# ensmartening.net
KiCad netlist of a schematic drawn in EasyEDA Pro
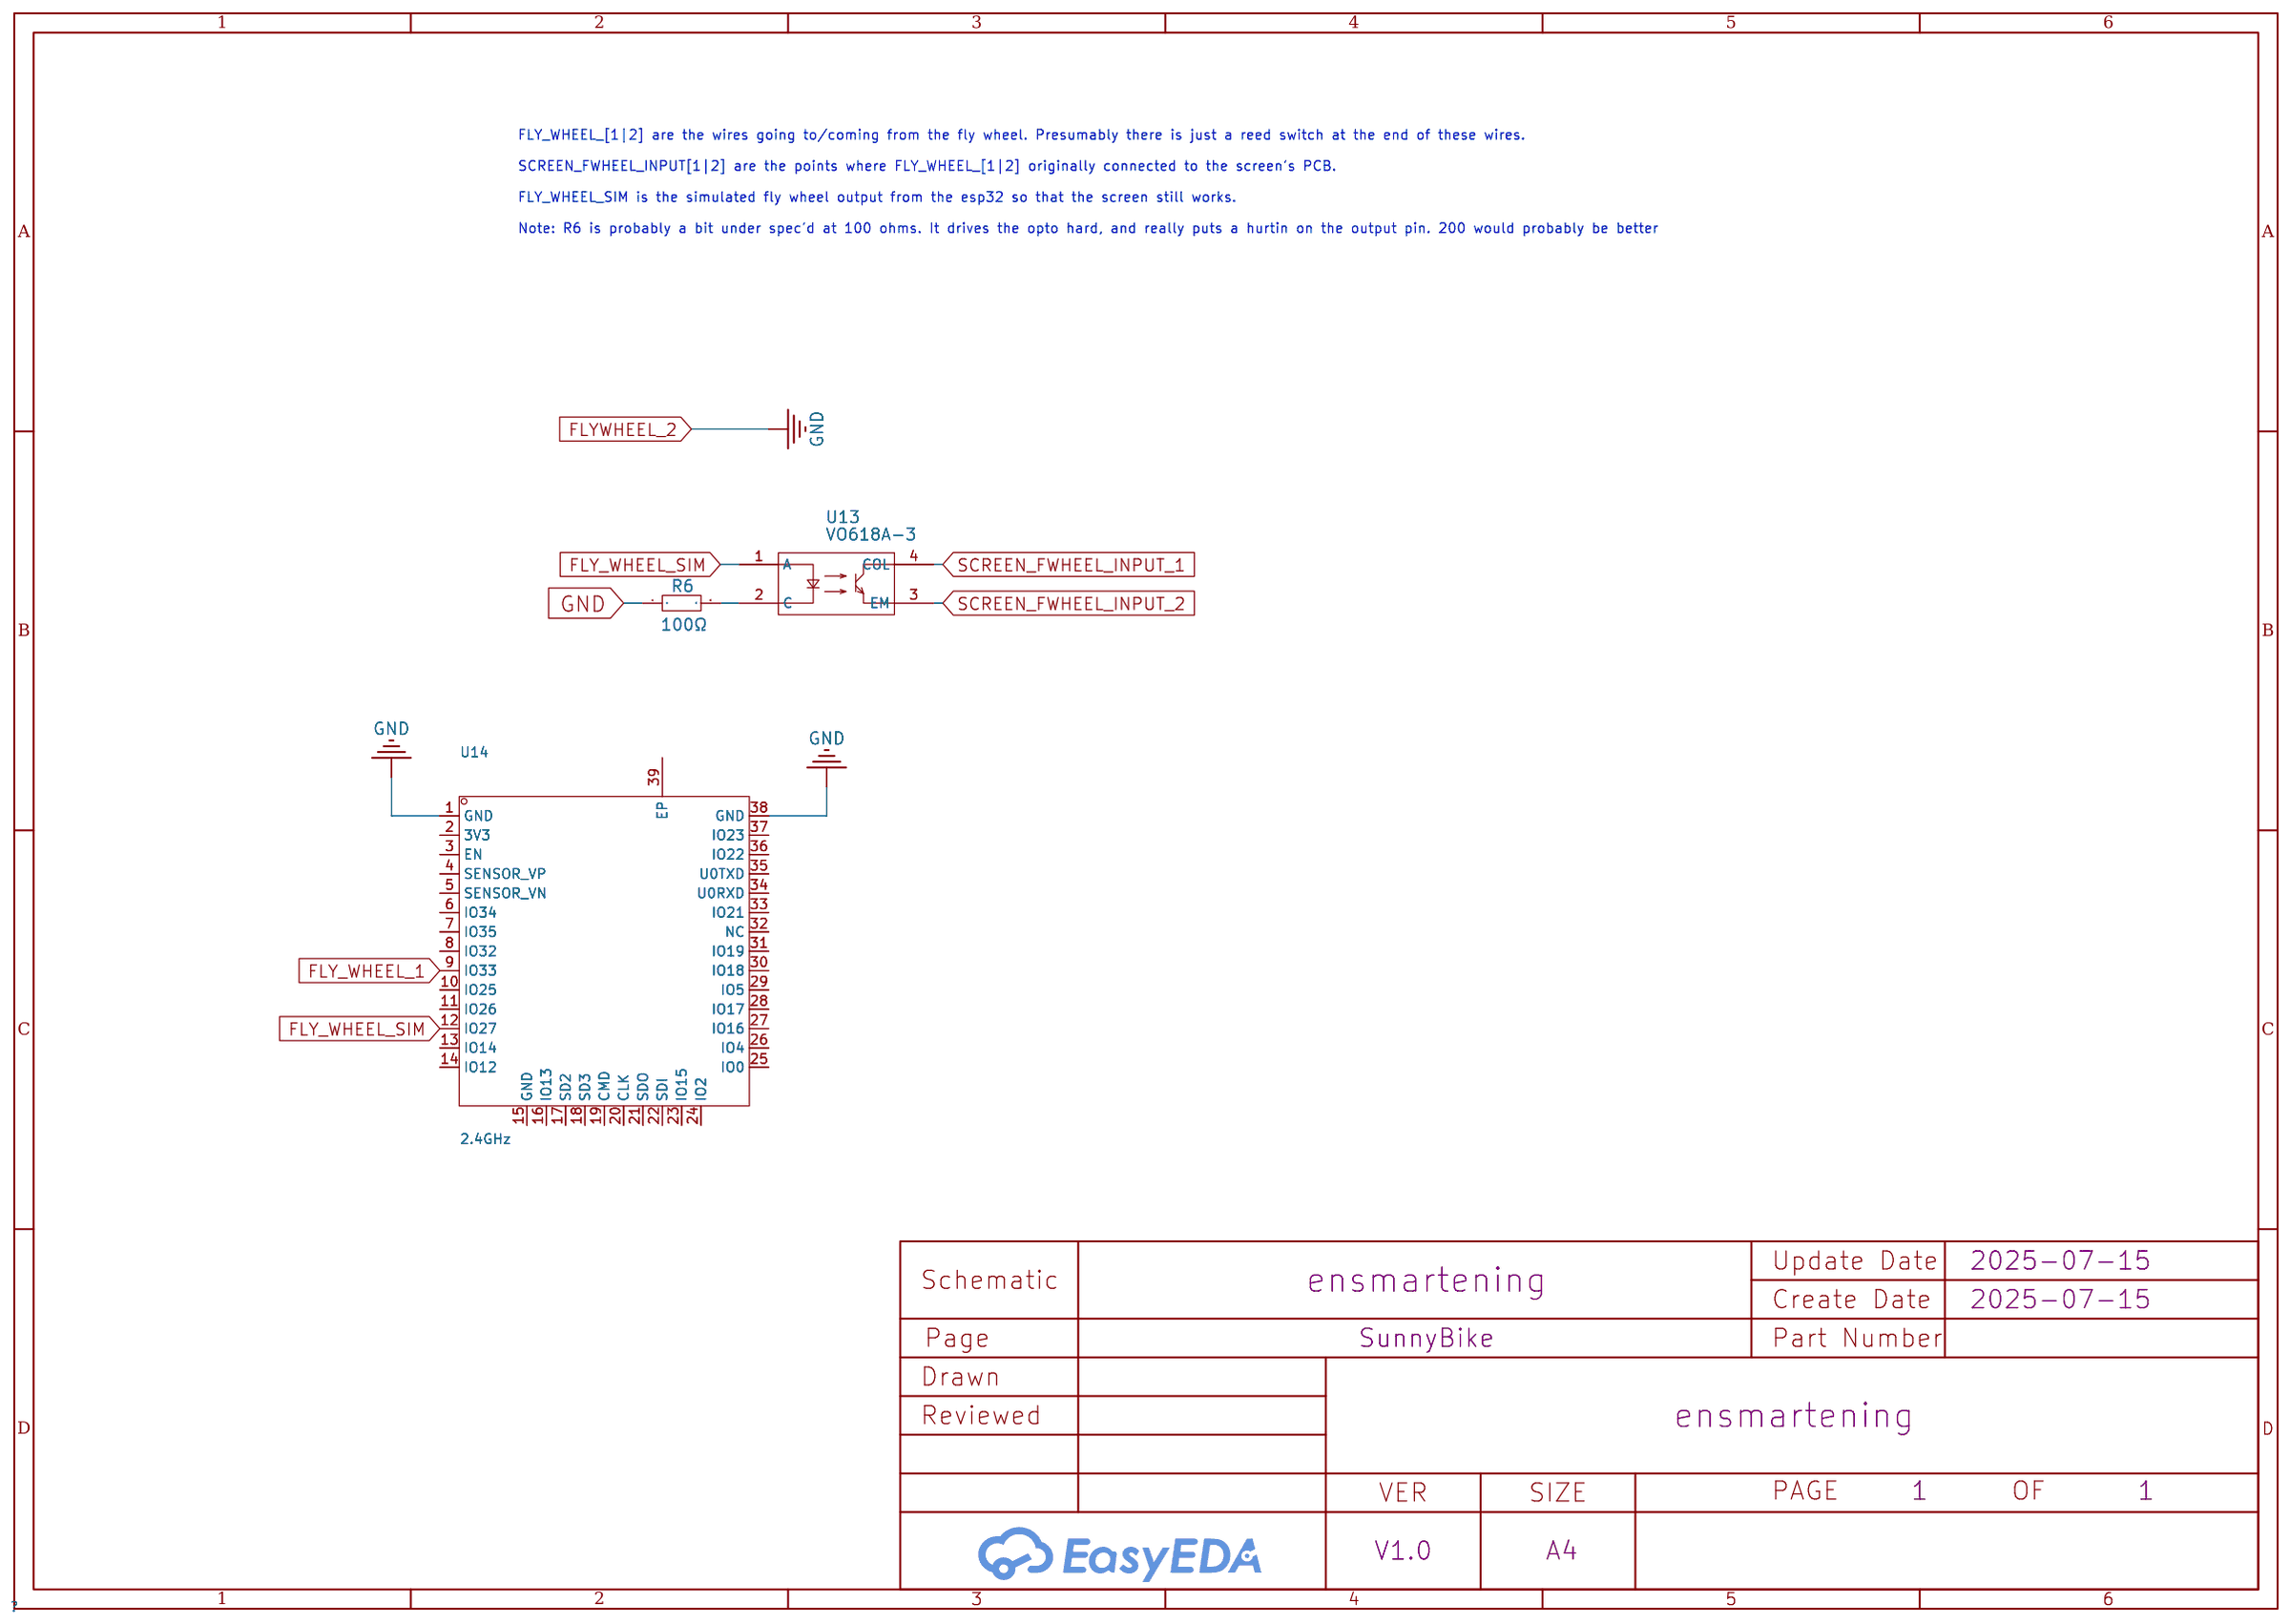
[diagram p0: schematic sheet]

(export (version "E")
  (design (tool "Eeschema 10.0.6"))
  (components
    (comp (ref "R6")
      (value "100Ω")
      (footprint "easyedapro:R0603")
      (fields (field (name "Manufacturer Part") "RC0603JR-07100RL") (field (name "Manufacturer") "YAGEO(国巨)"))
      (libsource (lib "easyedapro") (part "100Ω"))
    )
    (comp (ref "U13")
      (value "VO618A-3")
      (footprint "easyedapro:DIP-4_L6.4-W4.6-P2.54-LS7.6-BL")
      (fields (field (name "Manufacturer") "VISHAY(威世)"))
      (libsource (lib "easyedapro") (part "VO618A-3"))
    )
    (comp (ref "U14")
      (value "2.4GHz")
      (footprint "easyedapro:WIRELM-SMD_ESP32-S")
      (fields (field (name "Manufacturer Part") "ESP32-S") (field (name "Manufacturer") "Ai-Thinker(安信可)"))
      (libsource (lib "easyedapro") (part "ESP32-S"))
    )
  )
  (nets
    (net (code "1") (name "FLYWHEEL_2") (class "Default")
      (node (ref "R6") (pin "1") (pinfunction "1_1") (pintype "input"))
      (node (ref "U14") (pin "1") (pinfunction "GND_1") (pintype "input"))
      (node (ref "U14") (pin "38") (pinfunction "GND_38") (pintype "input"))
    )
    (net (code "2") (name "FLY_WHEEL_1") (class "Default")
      (node (ref "U14") (pin "9") (pinfunction "IO33_9") (pintype "input"))
    )
    (net (code "3") (name "FLY_WHEEL_SIM") (class "Default")
      (node (ref "U13") (pin "1") (pinfunction "A_1") (pintype "input"))
      (node (ref "U14") (pin "12") (pinfunction "IO27_12") (pintype "input"))
    )
    (net (code "4") (name "Net-(U13-C)") (class "Default")
      (node (ref "R6") (pin "2") (pinfunction "2_2") (pintype "input"))
      (node (ref "U13") (pin "2") (pinfunction "C_2") (pintype "input"))
    )
    (net (code "5") (name "SCREEN_FWHEEL_INPUT_1") (class "Default")
      (node (ref "U13") (pin "4") (pinfunction "COL_4") (pintype "input"))
    )
    (net (code "6") (name "SCREEN_FWHEEL_INPUT_2") (class "Default")
      (node (ref "U13") (pin "3") (pinfunction "EM_3") (pintype "input"))
    )
    (net (code "7") (name "unconnected-(U14-3V3-Pad2)") (class "Default")
      (node (ref "U14") (pin "2") (pinfunction "3V3_2") (pintype "input"))
    )
    (net (code "8") (name "unconnected-(U14-CLK-Pad20)") (class "Default")
      (node (ref "U14") (pin "20") (pinfunction "CLK_20") (pintype "input"))
    )
    (net (code "9") (name "unconnected-(U14-CMD-Pad19)") (class "Default")
      (node (ref "U14") (pin "19") (pinfunction "CMD_19") (pintype "input"))
    )
    (net (code "10") (name "unconnected-(U14-EN-Pad3)") (class "Default")
      (node (ref "U14") (pin "3") (pinfunction "EN_3") (pintype "input"))
    )
    (net (code "11") (name "unconnected-(U14-EP-Pad39)") (class "Default")
      (node (ref "U14") (pin "39") (pinfunction "EP_39") (pintype "input"))
    )
    (net (code "12") (name "unconnected-(U14-GND-Pad15)") (class "Default")
      (node (ref "U14") (pin "15") (pinfunction "GND_15") (pintype "input"))
    )
    (net (code "13") (name "unconnected-(U14-IO0-Pad25)") (class "Default")
      (node (ref "U14") (pin "25") (pinfunction "IO0_25") (pintype "input"))
    )
    (net (code "14") (name "unconnected-(U14-IO2-Pad24)") (class "Default")
      (node (ref "U14") (pin "24") (pinfunction "IO2_24") (pintype "input"))
    )
    (net (code "15") (name "unconnected-(U14-IO4-Pad26)") (class "Default")
      (node (ref "U14") (pin "26") (pinfunction "IO4_26") (pintype "input"))
    )
    (net (code "16") (name "unconnected-(U14-IO5-Pad29)") (class "Default")
      (node (ref "U14") (pin "29") (pinfunction "IO5_29") (pintype "input"))
    )
    (net (code "17") (name "unconnected-(U14-IO12-Pad14)") (class "Default")
      (node (ref "U14") (pin "14") (pinfunction "IO12_14") (pintype "input"))
    )
    (net (code "18") (name "unconnected-(U14-IO13-Pad16)") (class "Default")
      (node (ref "U14") (pin "16") (pinfunction "IO13_16") (pintype "input"))
    )
    (net (code "19") (name "unconnected-(U14-IO14-Pad13)") (class "Default")
      (node (ref "U14") (pin "13") (pinfunction "IO14_13") (pintype "input"))
    )
    (net (code "20") (name "unconnected-(U14-IO15-Pad23)") (class "Default")
      (node (ref "U14") (pin "23") (pinfunction "IO15_23") (pintype "input"))
    )
    (net (code "21") (name "unconnected-(U14-IO16-Pad27)") (class "Default")
      (node (ref "U14") (pin "27") (pinfunction "IO16_27") (pintype "input"))
    )
    (net (code "22") (name "unconnected-(U14-IO17-Pad28)") (class "Default")
      (node (ref "U14") (pin "28") (pinfunction "IO17_28") (pintype "input"))
    )
    (net (code "23") (name "unconnected-(U14-IO18-Pad30)") (class "Default")
      (node (ref "U14") (pin "30") (pinfunction "IO18_30") (pintype "input"))
    )
    (net (code "24") (name "unconnected-(U14-IO19-Pad31)") (class "Default")
      (node (ref "U14") (pin "31") (pinfunction "IO19_31") (pintype "input"))
    )
    (net (code "25") (name "unconnected-(U14-IO21-Pad33)") (class "Default")
      (node (ref "U14") (pin "33") (pinfunction "IO21_33") (pintype "input"))
    )
    (net (code "26") (name "unconnected-(U14-IO22-Pad36)") (class "Default")
      (node (ref "U14") (pin "36") (pinfunction "IO22_36") (pintype "input"))
    )
    (net (code "27") (name "unconnected-(U14-IO23-Pad37)") (class "Default")
      (node (ref "U14") (pin "37") (pinfunction "IO23_37") (pintype "input"))
    )
    (net (code "28") (name "unconnected-(U14-IO25-Pad10)") (class "Default")
      (node (ref "U14") (pin "10") (pinfunction "IO25_10") (pintype "input"))
    )
    (net (code "29") (name "unconnected-(U14-IO26-Pad11)") (class "Default")
      (node (ref "U14") (pin "11") (pinfunction "IO26_11") (pintype "input"))
    )
    (net (code "30") (name "unconnected-(U14-IO32-Pad8)") (class "Default")
      (node (ref "U14") (pin "8") (pinfunction "IO32_8") (pintype "input"))
    )
    (net (code "31") (name "unconnected-(U14-IO34-Pad6)") (class "Default")
      (node (ref "U14") (pin "6") (pinfunction "IO34_6") (pintype "input"))
    )
    (net (code "32") (name "unconnected-(U14-IO35-Pad7)") (class "Default")
      (node (ref "U14") (pin "7") (pinfunction "IO35_7") (pintype "input"))
    )
    (net (code "33") (name "unconnected-(U14-NC-Pad32)") (class "Default")
      (node (ref "U14") (pin "32") (pinfunction "NC_32") (pintype "input"))
    )
    (net (code "34") (name "unconnected-(U14-SD2-Pad17)") (class "Default")
      (node (ref "U14") (pin "17") (pinfunction "SD2_17") (pintype "input"))
    )
    (net (code "35") (name "unconnected-(U14-SD3-Pad18)") (class "Default")
      (node (ref "U14") (pin "18") (pinfunction "SD3_18") (pintype "input"))
    )
    (net (code "36") (name "unconnected-(U14-SDI-Pad22)") (class "Default")
      (node (ref "U14") (pin "22") (pinfunction "SDI_22") (pintype "input"))
    )
    (net (code "37") (name "unconnected-(U14-SDO-Pad21)") (class "Default")
      (node (ref "U14") (pin "21") (pinfunction "SDO_21") (pintype "input"))
    )
    (net (code "38") (name "unconnected-(U14-SENSOR_VN-Pad5)") (class "Default")
      (node (ref "U14") (pin "5") (pinfunction "SENSOR_VN_5") (pintype "input"))
    )
    (net (code "39") (name "unconnected-(U14-SENSOR_VP-Pad4)") (class "Default")
      (node (ref "U14") (pin "4") (pinfunction "SENSOR_VP_4") (pintype "input"))
    )
    (net (code "40") (name "unconnected-(U14-U0RXD-Pad34)") (class "Default")
      (node (ref "U14") (pin "34") (pinfunction "U0RXD_34") (pintype "input"))
    )
    (net (code "41") (name "unconnected-(U14-U0TXD-Pad35)") (class "Default")
      (node (ref "U14") (pin "35") (pinfunction "U0TXD_35") (pintype "input"))
    )
  )
)
